# start.net
KiCad netlist of a schematic drawn in EAGLE
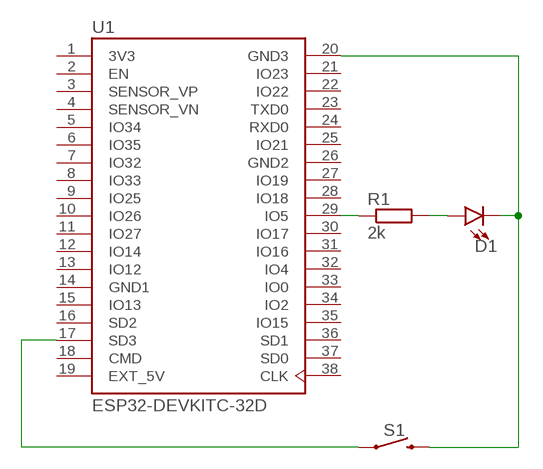
[diagram p0: schematic, sheet 1]

(export (version "E")
  (design (tool "Eeschema 10.0.6"))
  (components
    (comp (ref "D1")
      (value "LED5MM")
      (footprint "eagle-import:LED_5MM")
      (libsource (lib "eagle-import") (part "LED5MM"))
    )
    (comp (ref "R1")
      (value "2k")
      (footprint "eagle-import:0204_5")
      (libsource (lib "eagle-import") (part "R-EU_0204/5"))
    )
    (comp (ref "S1")
      (value "MOMENTARY-SWITCH-SPST-PTH-6.0MM")
      (footprint "eagle-import:TACTILE_SWITCH_PTH_6.0MM")
      (libsource (lib "eagle-import") (part "MOMENTARY-SWITCH-SPST-PTH-6.0MM"))
    )
    (comp (ref "U1")
      (value "ESP32-DEVKITC-32D")
      (footprint "eagle-import:MODULE_ESP32-DEVKITC-32D")
      (fields (field (name "MF") "Espressif Systems"))
      (libsource (lib "eagle-import") (part "ESP32-DEVKITC-32D"))
    )
  )
  (nets
    (net (code "1") (name "/3V3") (class "Default")
      (node (ref "U1") (pin "1") (pinfunction "3V3_1") (pintype "power_in"))
    )
    (net (code "2") (name "/EXT_5V") (class "Default")
      (node (ref "U1") (pin "19") (pinfunction "EXT_5V_19") (pintype "power_in"))
    )
    (net (code "3") (name "/GND1") (class "Default")
      (node (ref "U1") (pin "14") (pinfunction "GND1_14") (pintype "power_in"))
    )
    (net (code "4") (name "/GND2") (class "Default")
      (node (ref "U1") (pin "26") (pinfunction "GND2_26") (pintype "power_in"))
    )
    (net (code "5") (name "Net-(D1-C)") (class "Default")
      (node (ref "D1") (pin "K") (pinfunction "C_K") (pintype "passive"))
      (node (ref "S1") (pin "3") (pinfunction "2_3") (pintype "passive"))
      (node (ref "U1") (pin "20") (pinfunction "GND3_20") (pintype "power_in"))
    )
    (net (code "6") (name "Net-(D1-PadA)") (class "Default")
      (node (ref "D1") (pin "A") (pinfunction "A_A") (pintype "passive"))
      (node (ref "R1") (pin "2") (pinfunction "2_2") (pintype "passive"))
    )
    (net (code "7") (name "Net-(U1-IO5)") (class "Default")
      (node (ref "R1") (pin "1") (pinfunction "1_1") (pintype "passive"))
      (node (ref "U1") (pin "29") (pinfunction "IO5_29") (pintype "bidirectional"))
    )
    (net (code "8") (name "Net-(U1-SD3)") (class "Default")
      (node (ref "S1") (pin "1") (pinfunction "1_1") (pintype "passive"))
      (node (ref "U1") (pin "17") (pinfunction "SD3_17") (pintype "bidirectional"))
    )
    (net (code "9") (name "unconnected-(U1-CLK-Pad38)") (class "Default")
      (node (ref "U1") (pin "38") (pinfunction "CLK_38") (pintype "input"))
    )
    (net (code "10") (name "unconnected-(U1-CMD-Pad18)") (class "Default")
      (node (ref "U1") (pin "18") (pinfunction "CMD_18") (pintype "bidirectional"))
    )
    (net (code "11") (name "unconnected-(U1-EN-Pad2)") (class "Default")
      (node (ref "U1") (pin "2") (pinfunction "EN_2") (pintype "input"))
    )
    (net (code "12") (name "unconnected-(U1-IO0-Pad33)") (class "Default")
      (node (ref "U1") (pin "33") (pinfunction "IO0_33") (pintype "bidirectional"))
    )
    (net (code "13") (name "unconnected-(U1-IO2-Pad34)") (class "Default")
      (node (ref "U1") (pin "34") (pinfunction "IO2_34") (pintype "bidirectional"))
    )
    (net (code "14") (name "unconnected-(U1-IO4-Pad32)") (class "Default")
      (node (ref "U1") (pin "32") (pinfunction "IO4_32") (pintype "bidirectional"))
    )
    (net (code "15") (name "unconnected-(U1-IO12-Pad13)") (class "Default")
      (node (ref "U1") (pin "13") (pinfunction "IO12_13") (pintype "bidirectional"))
    )
    (net (code "16") (name "unconnected-(U1-IO13-Pad15)") (class "Default")
      (node (ref "U1") (pin "15") (pinfunction "IO13_15") (pintype "bidirectional"))
    )
    (net (code "17") (name "unconnected-(U1-IO14-Pad12)") (class "Default")
      (node (ref "U1") (pin "12") (pinfunction "IO14_12") (pintype "bidirectional"))
    )
    (net (code "18") (name "unconnected-(U1-IO15-Pad35)") (class "Default")
      (node (ref "U1") (pin "35") (pinfunction "IO15_35") (pintype "bidirectional"))
    )
    (net (code "19") (name "unconnected-(U1-IO16-Pad31)") (class "Default")
      (node (ref "U1") (pin "31") (pinfunction "IO16_31") (pintype "bidirectional"))
    )
    (net (code "20") (name "unconnected-(U1-IO17-Pad30)") (class "Default")
      (node (ref "U1") (pin "30") (pinfunction "IO17_30") (pintype "bidirectional"))
    )
    (net (code "21") (name "unconnected-(U1-IO18-Pad28)") (class "Default")
      (node (ref "U1") (pin "28") (pinfunction "IO18_28") (pintype "bidirectional"))
    )
    (net (code "22") (name "unconnected-(U1-IO19-Pad27)") (class "Default")
      (node (ref "U1") (pin "27") (pinfunction "IO19_27") (pintype "bidirectional"))
    )
    (net (code "23") (name "unconnected-(U1-IO21-Pad25)") (class "Default")
      (node (ref "U1") (pin "25") (pinfunction "IO21_25") (pintype "bidirectional"))
    )
    (net (code "24") (name "unconnected-(U1-IO22-Pad22)") (class "Default")
      (node (ref "U1") (pin "22") (pinfunction "IO22_22") (pintype "bidirectional"))
    )
    (net (code "25") (name "unconnected-(U1-IO23-Pad21)") (class "Default")
      (node (ref "U1") (pin "21") (pinfunction "IO23_21") (pintype "bidirectional"))
    )
    (net (code "26") (name "unconnected-(U1-IO25-Pad9)") (class "Default")
      (node (ref "U1") (pin "9") (pinfunction "IO25_9") (pintype "bidirectional"))
    )
    (net (code "27") (name "unconnected-(U1-IO26-Pad10)") (class "Default")
      (node (ref "U1") (pin "10") (pinfunction "IO26_10") (pintype "bidirectional"))
    )
    (net (code "28") (name "unconnected-(U1-IO27-Pad11)") (class "Default")
      (node (ref "U1") (pin "11") (pinfunction "IO27_11") (pintype "bidirectional"))
    )
    (net (code "29") (name "unconnected-(U1-IO32-Pad7)") (class "Default")
      (node (ref "U1") (pin "7") (pinfunction "IO32_7") (pintype "bidirectional"))
    )
    (net (code "30") (name "unconnected-(U1-IO33-Pad8)") (class "Default")
      (node (ref "U1") (pin "8") (pinfunction "IO33_8") (pintype "bidirectional"))
    )
    (net (code "31") (name "unconnected-(U1-IO34-Pad5)") (class "Default")
      (node (ref "U1") (pin "5") (pinfunction "IO34_5") (pintype "bidirectional"))
    )
    (net (code "32") (name "unconnected-(U1-IO35-Pad6)") (class "Default")
      (node (ref "U1") (pin "6") (pinfunction "IO35_6") (pintype "bidirectional"))
    )
    (net (code "33") (name "unconnected-(U1-RXD0-Pad24)") (class "Default")
      (node (ref "U1") (pin "24") (pinfunction "RXD0_24") (pintype "input"))
    )
    (net (code "34") (name "unconnected-(U1-SD0-Pad37)") (class "Default")
      (node (ref "U1") (pin "37") (pinfunction "SD0_37") (pintype "bidirectional"))
    )
    (net (code "35") (name "unconnected-(U1-SD1-Pad36)") (class "Default")
      (node (ref "U1") (pin "36") (pinfunction "SD1_36") (pintype "bidirectional"))
    )
    (net (code "36") (name "unconnected-(U1-SD2-Pad16)") (class "Default")
      (node (ref "U1") (pin "16") (pinfunction "SD2_16") (pintype "bidirectional"))
    )
    (net (code "37") (name "unconnected-(U1-SENSOR_VN-Pad4)") (class "Default")
      (node (ref "U1") (pin "4") (pinfunction "SENSOR_VN_4") (pintype "input"))
    )
    (net (code "38") (name "unconnected-(U1-SENSOR_VP-Pad3)") (class "Default")
      (node (ref "U1") (pin "3") (pinfunction "SENSOR_VP_3") (pintype "input"))
    )
    (net (code "39") (name "unconnected-(U1-TXD0-Pad23)") (class "Default")
      (node (ref "U1") (pin "23") (pinfunction "TXD0_23") (pintype "output"))
    )
  )
)
